# Power.net
KiCad netlist of a schematic drawn in Altium Designer
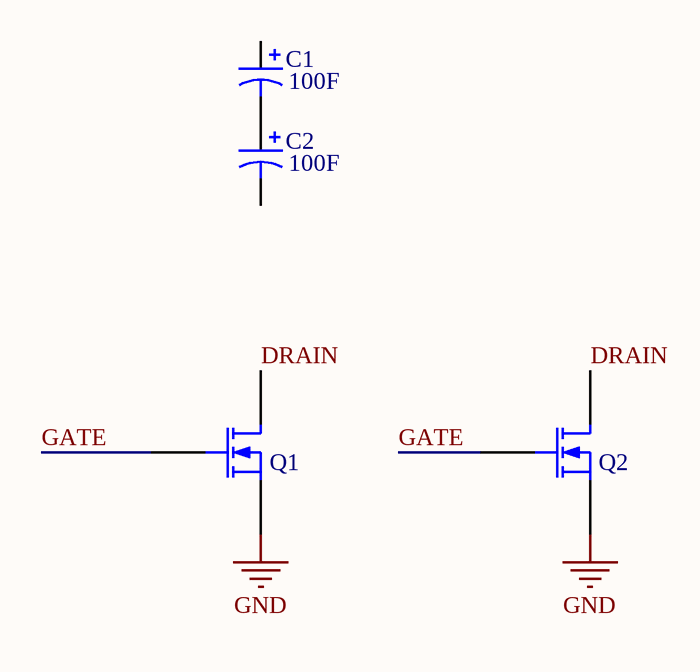
[diagram p0: Power.SchDoc]

(export (version "E")
  (design (tool "Eeschema 10.0.6"))
  (components
    (comp (ref "C1")
      (value "100F")
      (footprint "CAP")
      (description "Polarized Capacitor (Axial)")
      (fields (field (name "PUBLISHER") "Altium Limited"))
      (libsource (lib "Components") (part "CAP"))
    )
    (comp (ref "C2")
      (value "100F")
      (footprint "CAP")
      (description "Polarized Capacitor (Axial)")
      (fields (field (name "PUBLISHER") "Altium Limited"))
      (libsource (lib "Components") (part "CAP"))
    )
    (comp (ref "Q1")
      (value "MOSFET-N")
      (footprint "TO220V")
      (description "N-Channel MOSFET")
      (fields (field (name "PUBLISHER") "Altium Limited"))
      (libsource (lib "Components") (part "MOSFET-N"))
    )
    (comp (ref "Q2")
      (value "MOSFET-N")
      (footprint "TO220V")
      (description "N-Channel MOSFET")
      (fields (field (name "PUBLISHER") "Altium Limited"))
      (libsource (lib "Components") (part "MOSFET-N"))
    )
  )
  (nets
    (net (code "1") (name "/DRAIN") (class "Default")
      (node (ref "Q1") (pin "2") (pinfunction "D_2") (pintype "passive"))
      (node (ref "Q2") (pin "2") (pinfunction "D_2") (pintype "passive"))
    )
    (net (code "2") (name "/GATE") (class "Default")
      (node (ref "Q1") (pin "1") (pinfunction "G_1") (pintype "passive"))
      (node (ref "Q2") (pin "1") (pinfunction "G_1") (pintype "passive"))
    )
    (net (code "3") (name "GND") (class "Default")
      (node (ref "Q1") (pin "3") (pinfunction "S_3") (pintype "passive"))
      (node (ref "Q2") (pin "3") (pinfunction "S_3") (pintype "passive"))
    )
    (net (code "4") (name "Net-(C1-Pad2)") (class "Default")
      (node (ref "C1") (pin "2") (pinfunction "2_2") (pintype "passive"))
      (node (ref "C2") (pin "1") (pinfunction "1_1") (pintype "passive"))
    )
    (net (code "5") (name "unconnected-(C1-Pad1)") (class "Default")
      (node (ref "C1") (pin "1") (pinfunction "1_1") (pintype "passive"))
    )
    (net (code "6") (name "unconnected-(C2-Pad2)") (class "Default")
      (node (ref "C2") (pin "2") (pinfunction "2_2") (pintype "passive"))
    )
  )
)
